# Sheet1.net
KiCad netlist of a schematic drawn in Altium Designer
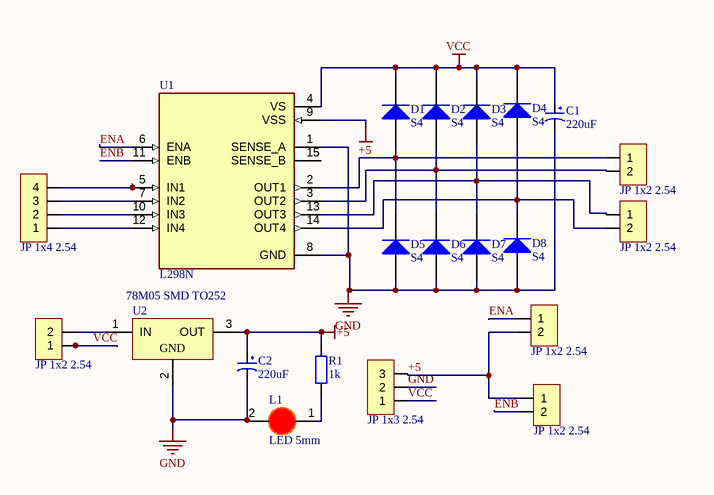
[diagram p0: Sheet1.SchDoc]

(export (version "E")
  (design (tool "Eeschema 10.0.6"))
  (components
    (comp (ref "C1")
      (value "220uF")
      (footprint "tu hoa 5mm")
      (description "Cắm")
      (libsource (lib "Altium_Lib_by_KhueNguyenCreator") (part "Tu Hoa 100uF 16V 5x7"))
    )
    (comp (ref "C2")
      (value "220uF")
      (footprint "tu hoa 5mm")
      (description "Cắm")
      (libsource (lib "Altium_Lib_by_KhueNguyenCreator") (part "Tu Hoa 100uF 16V 5x7"))
    )
    (comp (ref "D1")
      (value "S4")
      (footprint "DIODE SOD-123")
      (description "Dán")
      (libsource (lib "Altium_Lib_by_KhueNguyenCreator") (part "Diode S4"))
    )
    (comp (ref "D2")
      (value "S4")
      (footprint "DIODE SOD-123")
      (description "Dán")
      (libsource (lib "Altium_Lib_by_KhueNguyenCreator") (part "Diode S4"))
    )
    (comp (ref "D3")
      (value "S4")
      (footprint "DIODE SOD-123")
      (description "Dán")
      (libsource (lib "Altium_Lib_by_KhueNguyenCreator") (part "Diode S4"))
    )
    (comp (ref "D4")
      (value "S4")
      (footprint "DIODE SOD-123")
      (description "Dán")
      (libsource (lib "Altium_Lib_by_KhueNguyenCreator") (part "Diode S4"))
    )
    (comp (ref "D5")
      (value "S4")
      (footprint "DIODE SOD-123")
      (description "Dán")
      (libsource (lib "Altium_Lib_by_KhueNguyenCreator") (part "Diode S4"))
    )
    (comp (ref "D6")
      (value "S4")
      (footprint "DIODE SOD-123")
      (description "Dán")
      (libsource (lib "Altium_Lib_by_KhueNguyenCreator") (part "Diode S4"))
    )
    (comp (ref "D7")
      (value "S4")
      (footprint "DIODE SOD-123")
      (description "Dán")
      (libsource (lib "Altium_Lib_by_KhueNguyenCreator") (part "Diode S4"))
    )
    (comp (ref "D8")
      (value "S4")
      (footprint "DIODE SOD-123")
      (description "Dán")
      (libsource (lib "Altium_Lib_by_KhueNguyenCreator") (part "Diode S4"))
    )
    (comp (ref "JP1")
      (value "JP 1x2 2.54")
      (footprint "JP 1x2 CT")
      (description "Cắm")
      (libsource (lib "Altium_Lib_by_KhueNguyenCreator") (part "JP 1x2 2.54 Cai Thang"))
    )
    (comp (ref "JP2")
      (value "JP 1x4 2.54")
      (footprint "JP 1x4 DT")
      (description "Cắm")
      (libsource (lib "Altium_Lib_by_KhueNguyenCreator") (part "JP 1x4 2.54 Duc Thang"))
    )
    (comp (ref "JP3")
      (value "JP 1x2 2.54")
      (footprint "JP 1x2 CT")
      (description "Cắm")
      (libsource (lib "Altium_Lib_by_KhueNguyenCreator") (part "JP 1x2 2.54 Cai Thang"))
    )
    (comp (ref "JP4")
      (value "JP 1x2 2.54")
      (footprint "JP 1x2 CT")
      (description "Cắm")
      (libsource (lib "Altium_Lib_by_KhueNguyenCreator") (part "JP 1x2 2.54 Cai Thang"))
    )
    (comp (ref "JP5")
      (value "JP 1x2 2.54")
      (footprint "JP 1x2 CT")
      (description "Cắm")
      (libsource (lib "") (part "JP 1x2 2.54 Cai Thang_1"))
    )
    (comp (ref "JP6")
      (value "JP 1x3 2.54")
      (footprint "JP 1x3 CT")
      (description "Cắm")
      (libsource (lib "Altium_Lib_by_KhueNguyenCreator") (part "JP 1x3 2.54 Cai Thang"))
    )
    (comp (ref "JP7")
      (value "JP 1x2 2.54")
      (footprint "JP 1x2 CT")
      (description "Cắm")
      (libsource (lib "Altium_Lib_by_KhueNguyenCreator") (part "JP 1x2 2.54 Cai Thang"))
    )
    (comp (ref "L1")
      (value "LED 5mm")
      (footprint "LED-5MM-RED")
      (description "Cắm")
      (libsource (lib "Altium_Lib_by_KhueNguyenCreator") (part "LED 5mm Do"))
    )
    (comp (ref "R1")
      (value "1k")
      (footprint "tro vach 1/2w")
      (description "Cắm")
      (libsource (lib "Altium_Lib_by_KhueNguyenCreator") (part "Tro Vach 1/2W 5% 270R"))
    )
    (comp (ref "U1")
      (value "L298N")
      (footprint "TO127P2020X500X2100-15")
      (description "Dual Full Bridge Motor Driver 15-Pin(15+Tab) MULTIWATT V Tube")
      (libsource (lib "L298N") (part "L298N"))
    )
    (comp (ref "U2")
      (value "78M05 SMD TO252")
      (footprint "TO252")
      (description "Dán")
      (libsource (lib "Altium_Lib_by_KhueNguyenCreator") (part "78M05 SMD TO252"))
    )
  )
  (nets
    (net (code "1") (name "+5") (class "Default")
      (node (ref "C2") (pin "1") (pinfunction "1_1") (pintype "passive"))
      (node (ref "JP4") (pin "2") (pinfunction "2_2") (pintype "passive"))
      (node (ref "JP6") (pin "3") (pinfunction "3_3") (pintype "passive"))
      (node (ref "JP7") (pin "1") (pinfunction "1_1") (pintype "passive"))
      (node (ref "R1") (pin "2") (pinfunction "2_2") (pintype "passive"))
      (node (ref "U1") (pin "9") (pinfunction "VSS_9") (pintype "input"))
      (node (ref "U2") (pin "3") (pinfunction "OUT_3") (pintype "power_in"))
    )
    (net (code "2") (name "/ENA") (class "Default")
      (node (ref "JP4") (pin "1") (pinfunction "1_1") (pintype "passive"))
      (node (ref "U1") (pin "6") (pinfunction "ENA_6") (pintype "input"))
    )
    (net (code "3") (name "/ENB") (class "Default")
      (node (ref "JP7") (pin "2") (pinfunction "2_2") (pintype "passive"))
      (node (ref "U1") (pin "11") (pinfunction "ENB_11") (pintype "input"))
    )
    (net (code "4") (name "GND") (class "Default")
      (node (ref "C1") (pin "2") (pinfunction "2_2") (pintype "passive"))
      (node (ref "C2") (pin "2") (pinfunction "2_2") (pintype "passive"))
      (node (ref "D5") (pin "1") (pinfunction "A_1") (pintype "passive"))
      (node (ref "D6") (pin "1") (pinfunction "A_1") (pintype "passive"))
      (node (ref "D7") (pin "1") (pinfunction "A_1") (pintype "passive"))
      (node (ref "D8") (pin "1") (pinfunction "A_1") (pintype "passive"))
      (node (ref "JP6") (pin "2") (pinfunction "2_2") (pintype "passive"))
      (node (ref "L1") (pin "2") (pinfunction "K_2") (pintype "passive"))
      (node (ref "U1") (pin "1") (pinfunction "SENSE_A_1") (pintype "passive"))
      (node (ref "U1") (pin "8") (pinfunction "GND_8") (pintype "power_in"))
      (node (ref "U2") (pin "2") (pinfunction "GND_2") (pintype "power_in"))
    )
    (net (code "5") (name "Net-(D1-A)") (class "Default")
      (node (ref "D1") (pin "1") (pinfunction "A_1") (pintype "passive"))
      (node (ref "D5") (pin "2") (pinfunction "K_2") (pintype "passive"))
      (node (ref "JP1") (pin "1") (pinfunction "1_1") (pintype "passive"))
      (node (ref "U1") (pin "2") (pinfunction "OUT1_2") (pintype "output"))
    )
    (net (code "6") (name "Net-(D2-A)") (class "Default")
      (node (ref "D2") (pin "1") (pinfunction "A_1") (pintype "passive"))
      (node (ref "D6") (pin "2") (pinfunction "K_2") (pintype "passive"))
      (node (ref "JP1") (pin "2") (pinfunction "2_2") (pintype "passive"))
      (node (ref "U1") (pin "3") (pinfunction "OUT2_3") (pintype "output"))
    )
    (net (code "7") (name "Net-(D3-A)") (class "Default")
      (node (ref "D3") (pin "1") (pinfunction "A_1") (pintype "passive"))
      (node (ref "D7") (pin "2") (pinfunction "K_2") (pintype "passive"))
      (node (ref "JP3") (pin "1") (pinfunction "1_1") (pintype "passive"))
      (node (ref "U1") (pin "13") (pinfunction "OUT3_13") (pintype "output"))
    )
    (net (code "8") (name "Net-(D4-A)") (class "Default")
      (node (ref "D4") (pin "1") (pinfunction "A_1") (pintype "passive"))
      (node (ref "D8") (pin "2") (pinfunction "K_2") (pintype "passive"))
      (node (ref "JP3") (pin "2") (pinfunction "2_2") (pintype "passive"))
      (node (ref "U1") (pin "14") (pinfunction "OUT4_14") (pintype "output"))
    )
    (net (code "9") (name "Net-(L1-A)") (class "Default")
      (node (ref "L1") (pin "1") (pinfunction "A_1") (pintype "passive"))
      (node (ref "R1") (pin "1") (pinfunction "1_1") (pintype "passive"))
    )
    (net (code "10") (name "Net-(U1-IN1)") (class "Default")
      (node (ref "JP2") (pin "4") (pinfunction "4_4") (pintype "passive"))
      (node (ref "U1") (pin "5") (pinfunction "IN1_5") (pintype "input"))
    )
    (net (code "11") (name "Net-(U1-IN2)") (class "Default")
      (node (ref "JP2") (pin "3") (pinfunction "3_3") (pintype "passive"))
      (node (ref "U1") (pin "7") (pinfunction "IN2_7") (pintype "input"))
    )
    (net (code "12") (name "Net-(U1-IN3)") (class "Default")
      (node (ref "JP2") (pin "2") (pinfunction "2_2") (pintype "passive"))
      (node (ref "U1") (pin "10") (pinfunction "IN3_10") (pintype "input"))
    )
    (net (code "13") (name "Net-(U1-IN4)") (class "Default")
      (node (ref "JP2") (pin "1") (pinfunction "1_1") (pintype "passive"))
      (node (ref "U1") (pin "12") (pinfunction "IN4_12") (pintype "input"))
    )
    (net (code "14") (name "Net-(U2-IN)") (class "Default")
      (node (ref "JP5") (pin "2") (pinfunction "2_2") (pintype "passive"))
      (node (ref "U2") (pin "1") (pinfunction "IN_1") (pintype "power_in"))
    )
    (net (code "15") (name "VCC") (class "Default")
      (node (ref "C1") (pin "1") (pinfunction "1_1") (pintype "passive"))
      (node (ref "D1") (pin "2") (pinfunction "K_2") (pintype "passive"))
      (node (ref "D2") (pin "2") (pinfunction "K_2") (pintype "passive"))
      (node (ref "D3") (pin "2") (pinfunction "K_2") (pintype "passive"))
      (node (ref "D4") (pin "2") (pinfunction "K_2") (pintype "passive"))
      (node (ref "JP5") (pin "1") (pinfunction "1_1") (pintype "passive"))
      (node (ref "JP6") (pin "1") (pinfunction "1_1") (pintype "passive"))
      (node (ref "U1") (pin "4") (pinfunction "VS_4") (pintype "power_in"))
    )
    (net (code "16") (name "unconnected-(U1-SENSE_B-Pad15)") (class "Default")
      (node (ref "U1") (pin "15") (pinfunction "SENSE_B_15") (pintype "passive"))
    )
  )
)
